# WL_1_2G.net
KiCad netlist of a schematic drawn in Altium Designer
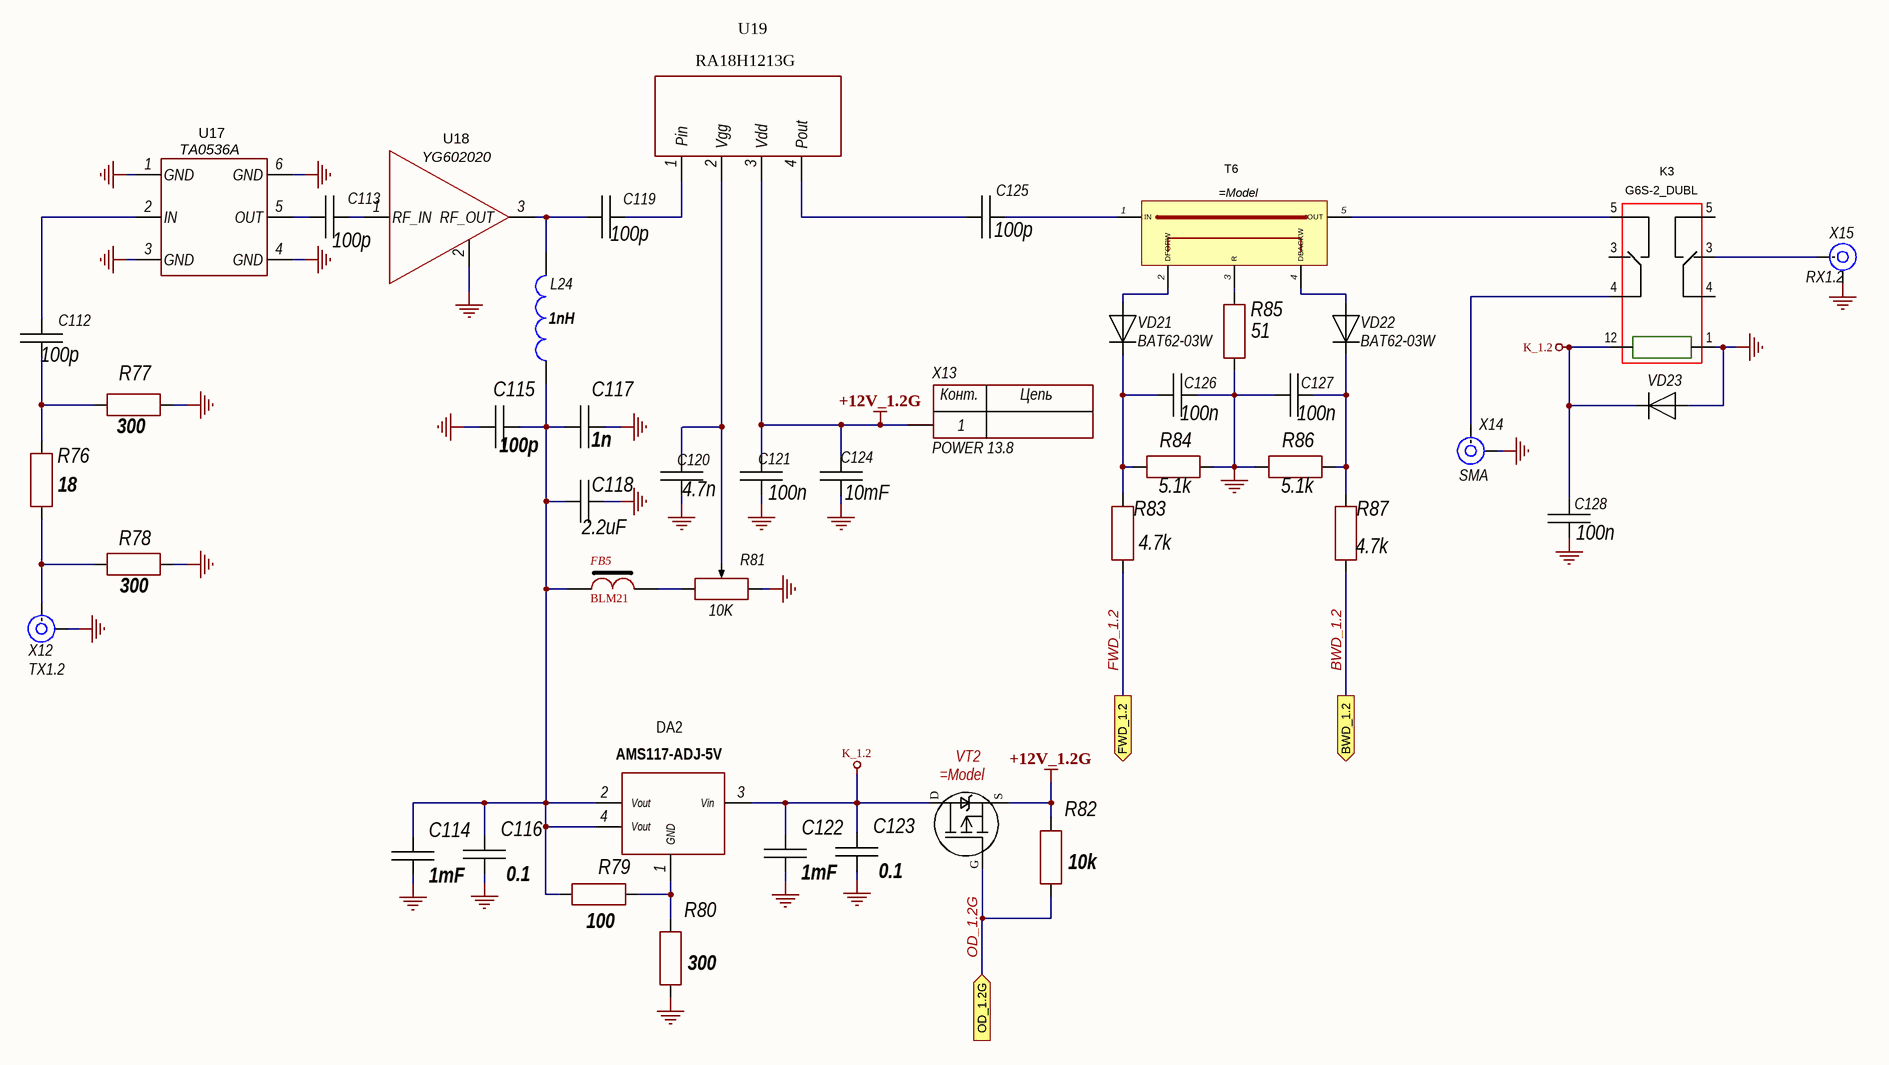
[diagram p0: WL_1.2G.SchDoc]

(export (version "E")
  (design (tool "Eeschema 10.0.6"))
  (components
    (comp (ref "C112")
      (value "100p")
      (footprint "standard:CH0603C")
      (libsource (lib "Discrete") (part "Capacitor"))
    )
    (comp (ref "C113")
      (value "100p")
      (footprint "standard:CH0603C")
      (libsource (lib "Discrete") (part "Capacitor"))
    )
    (comp (ref "C114")
      (value "1mF")
      (footprint "standard:CH0603C")
      (libsource (lib "Discrete") (part "Capacitor"))
    )
    (comp (ref "C115")
      (value "100p")
      (footprint "standard:CH0603C")
      (libsource (lib "Discrete") (part "Capacitor"))
    )
    (comp (ref "C116")
      (value "0.1")
      (footprint "standard:CH0805C")
      (libsource (lib "Discrete") (part "Capacitor"))
    )
    (comp (ref "C117")
      (value "1n")
      (footprint "standard:CH0603C")
      (libsource (lib "Discrete") (part "Capacitor"))
    )
    (comp (ref "C118")
      (value "2.2uF")
      (footprint "standard:CH0603C")
      (libsource (lib "Discrete") (part "Capacitor"))
    )
    (comp (ref "C119")
      (value "100p")
      (footprint "standard:CH0805C")
      (libsource (lib "Discrete") (part "Capacitor"))
    )
    (comp (ref "C120")
      (value "4.7n")
      (footprint "standard:CH0805C")
      (libsource (lib "Discrete") (part "Capacitor"))
    )
    (comp (ref "C121")
      (value "100n")
      (footprint "standard:CH1206C")
      (libsource (lib "Discrete") (part "Capacitor"))
    )
    (comp (ref "C122")
      (value "1mF")
      (footprint "standard:CH0805C")
      (libsource (lib "Discrete") (part "Capacitor"))
    )
    (comp (ref "C123")
      (value "0.1")
      (footprint "standard:CH0805C")
      (libsource (lib "Discrete") (part "Capacitor"))
    )
    (comp (ref "C124")
      (value "10mF")
      (footprint "standard:CH1206C")
      (libsource (lib "Discrete") (part "Capacitor"))
    )
    (comp (ref "C125")
      (value "100p")
      (footprint "standard:CH1210C")
      (libsource (lib "Discrete") (part "Capacitor"))
    )
    (comp (ref "C126")
      (value "100n")
      (footprint "standard:CH0603C")
      (libsource (lib "Discrete") (part "Capacitor"))
    )
    (comp (ref "C127")
      (value "100n")
      (footprint "standard:CH0603C")
      (libsource (lib "Discrete") (part "Capacitor"))
    )
    (comp (ref "C128")
      (value "100n")
      (footprint "standard:CH0805C")
      (libsource (lib "Discrete") (part "Capacitor"))
    )
    (comp (ref "DA2") (value "AMS117-ADJ-5V") (footprint "SOT223") (libsource (lib "Analog") (part "AMS117")))
    (comp (ref "FB5") (value "BLM21") (footprint "CH0805L") (libsource (lib "Discrete") (part "FB-1")))
    (comp (ref "K3")
      (value "G6S-2_DUBL")
      (footprint "G6S-2_DUBL")
      (libsource (lib "Relay") (part "G6S-2_DUBL"))
    )
    (comp (ref "L24")
      (value "1nH")
      (footprint "katuhka")
      (libsource (lib "Transformers") (part "Inductor ring"))
    )
    (comp (ref "R76")
      (value "18")
      (footprint "standard:CH0603R")
      (libsource (lib "Discrete") (part "Resistor"))
    )
    (comp (ref "R77") (value "300") (footprint "standard:CH0603R") (libsource (lib "") (part "Resistor_2")))
    (comp (ref "R78") (value "300") (footprint "standard:CH0603R") (libsource (lib "") (part "Resistor_2")))
    (comp (ref "R79") (value "100") (footprint "standard:CH0805R") (libsource (lib "") (part "Resistor_2")))
    (comp (ref "R80") (value "300") (footprint "standard:CH0805R") (libsource (lib "") (part "Resistor_1")))
    (comp (ref "R81")
      (value "10K")
      (footprint "custom:RES: 3296W")
      (libsource (lib "Discrete") (part "ADJ resistor"))
    )
    (comp (ref "R82") (value "10k") (footprint "standard:CH0805R") (libsource (lib "") (part "Resistor_1")))
    (comp (ref "R83")
      (value "4.7k")
      (footprint "standard:CH0603R")
      (libsource (lib "Discrete") (part "Resistor"))
    )
    (comp (ref "R84") (value "5.1k") (footprint "standard:CH0603R") (libsource (lib "") (part "Resistor_2")))
    (comp (ref "R85") (value "51") (footprint "standard:CH1206R") (libsource (lib "") (part "Resistor_1")))
    (comp (ref "R86") (value "5.1k") (footprint "standard:CH0603R") (libsource (lib "") (part "Resistor_2")))
    (comp (ref "R87")
      (value "4.7k")
      (footprint "standard:CH0603R")
      (libsource (lib "Discrete") (part "Resistor"))
    )
    (comp (ref "T6") (value "~") (footprint "SWR_D") (libsource (lib "Transformers") (part "VHF_KSV1")))
    (comp (ref "U17") (value "TA0536A") (footprint "MA08803") (libsource (lib "Digital") (part "TAU692")))
    (comp (ref "U18")
      (value "YG602020")
      (footprint "SOT89_123")
      (libsource (lib "Digital") (part "YG602020"))
    )
    (comp (ref "U19")
      (value "RA18H1213G")
      (footprint "RA80H1415M1 - duplicate")
      (libsource (lib "Digital") (part "RA80H1415M1"))
    )
    (comp (ref "VD21") (value "BAT62-03W") (footprint "1N4148") (libsource (lib "Diods") (part "Diod")))
    (comp (ref "VD22") (value "BAT62-03W") (footprint "1N4148") (libsource (lib "Diods") (part "Diod")))
    (comp (ref "VD23") (value "~") (footprint "1N4148") (libsource (lib "Diods") (part "Diod")))
    (comp (ref "VT2") (value "~") (footprint "SOT23_132") (libsource (lib "Transistor") (part "P-KANAL")))
    (comp (ref "X12")
      (value "TX1.2")
      (footprint "CON: u.Fl")
      (description "RF")
      (libsource (lib "Connectors") (part "SMA"))
    )
    (comp (ref "X13")
      (value "POWER 13.8")
      (footprint "CON: KNIFE_5MM")
      (libsource (lib "Connectors") (part "1-Connector"))
    )
    (comp (ref "X14")
      (value "SMA")
      (footprint "custom:CON: SMA")
      (description "RF")
      (libsource (lib "Connectors") (part "SMA"))
    )
    (comp (ref "X15")
      (value "RX1.2")
      (footprint "CON: u.Fl")
      (description "RF")
      (libsource (lib "Connectors") (part "SMA"))
    )
  )
  (nets
    (net (code "1") (name "+12V_1.2G") (class "Default")
      (node (ref "C121") (pin "2") (pinfunction "2_2") (pintype "power_in"))
      (node (ref "C124") (pin "2") (pinfunction "2_2") (pintype "power_in"))
      (node (ref "R82") (pin "2") (pinfunction "2_2") (pintype "passive"))
      (node (ref "U19") (pin "3") (pinfunction "Vdd_3") (pintype "passive"))
      (node (ref "VT2") (pin "2") (pinfunction "Исток_2") (pintype "passive"))
      (node (ref "X13") (pin "1") (pinfunction "1_1") (pintype "passive"))
    )
    (net (code "2") (name "/BWD_1.2") (class "Default")
      (node (ref "R87") (pin "2") (pinfunction "2_2") (pintype "passive"))
    )
    (net (code "3") (name "/FWD_1.2") (class "Default")
      (node (ref "R83") (pin "2") (pinfunction "2_2") (pintype "passive"))
    )
    (net (code "4") (name "/OD_1.2G") (class "Default")
      (node (ref "R82") (pin "1") (pinfunction "1_1") (pintype "passive"))
      (node (ref "VT2") (pin "1") (pinfunction "Затвор(Gate)_1") (pintype "passive"))
    )
    (net (code "5") (name "GND") (class "Default")
      (node (ref "C114") (pin "1") (pinfunction "1_1") (pintype "power_in"))
      (node (ref "C115") (pin "2") (pinfunction "2_2") (pintype "power_in"))
      (node (ref "C116") (pin "1") (pinfunction "1_1") (pintype "power_in"))
      (node (ref "C117") (pin "2") (pinfunction "2_2") (pintype "power_in"))
      (node (ref "C118") (pin "2") (pinfunction "2_2") (pintype "power_in"))
      (node (ref "C120") (pin "1") (pinfunction "1_1") (pintype "power_in"))
      (node (ref "C121") (pin "1") (pinfunction "1_1") (pintype "power_in"))
      (node (ref "C122") (pin "1") (pinfunction "1_1") (pintype "power_in"))
      (node (ref "C123") (pin "1") (pinfunction "1_1") (pintype "power_in"))
      (node (ref "C124") (pin "1") (pinfunction "1_1") (pintype "power_in"))
      (node (ref "C126") (pin "1") (pinfunction "1_1") (pintype "power_in"))
      (node (ref "C127") (pin "2") (pinfunction "2_2") (pintype "power_in"))
      (node (ref "C128") (pin "2") (pinfunction "2_2") (pintype "power_in"))
      (node (ref "K3") (pin "1") (pinfunction "1_1") (pintype "passive"))
      (node (ref "R77") (pin "1") (pinfunction "1_1") (pintype "passive"))
      (node (ref "R78") (pin "1") (pinfunction "1_1") (pintype "passive"))
      (node (ref "R80") (pin "1") (pinfunction "1_1") (pintype "passive"))
      (node (ref "R81") (pin "1") (pinfunction "1_1") (pintype "passive"))
      (node (ref "R84") (pin "1") (pinfunction "1_1") (pintype "passive"))
      (node (ref "R85") (pin "1") (pinfunction "1_1") (pintype "passive"))
      (node (ref "R86") (pin "2") (pinfunction "2_2") (pintype "passive"))
      (node (ref "U17") (pin "1") (pinfunction "GND_1") (pintype "passive"))
      (node (ref "U17") (pin "3") (pinfunction "GND_3") (pintype "passive"))
      (node (ref "U17") (pin "4") (pinfunction "GND_4") (pintype "passive"))
      (node (ref "U17") (pin "6") (pinfunction "GND_6") (pintype "passive"))
      (node (ref "U18") (pin "2") (pinfunction "GND_2") (pintype "passive"))
      (node (ref "VD23") (pin "1") (pinfunction "1_1") (pintype "passive"))
      (node (ref "X12") (pin "2") (pinfunction "IN_2") (pintype "passive"))
      (node (ref "X14") (pin "2") (pinfunction "IN_2") (pintype "passive"))
      (node (ref "X15") (pin "2") (pinfunction "IN_2") (pintype "passive"))
    )
    (net (code "6") (name "K_1.2") (class "Default")
      (node (ref "C122") (pin "2") (pinfunction "2_2") (pintype "power_in"))
      (node (ref "C123") (pin "2") (pinfunction "2_2") (pintype "power_in"))
      (node (ref "C128") (pin "1") (pinfunction "1_1") (pintype "power_in"))
      (node (ref "DA2") (pin "3") (pinfunction "Vin_3") (pintype "passive"))
      (node (ref "K3") (pin "12") (pinfunction "12_12") (pintype "passive"))
      (node (ref "VD23") (pin "2") (pinfunction "2_2") (pintype "passive"))
      (node (ref "VT2") (pin "3") (pinfunction "Сток_3") (pintype "passive"))
    )
    (net (code "7") (name "Net-(C112-Pad2)") (class "Default")
      (node (ref "C112") (pin "2") (pinfunction "2_2") (pintype "power_in"))
      (node (ref "R76") (pin "1") (pinfunction "1_1") (pintype "passive"))
      (node (ref "R77") (pin "2") (pinfunction "2_2") (pintype "passive"))
    )
    (net (code "8") (name "Net-(C114-Pad2)") (class "Default")
      (node (ref "C114") (pin "2") (pinfunction "2_2") (pintype "power_in"))
      (node (ref "C115") (pin "1") (pinfunction "1_1") (pintype "power_in"))
      (node (ref "C116") (pin "2") (pinfunction "2_2") (pintype "power_in"))
      (node (ref "C117") (pin "1") (pinfunction "1_1") (pintype "power_in"))
      (node (ref "C118") (pin "1") (pinfunction "1_1") (pintype "power_in"))
      (node (ref "DA2") (pin "2") (pinfunction "Vout_2") (pintype "passive"))
      (node (ref "DA2") (pin "4") (pinfunction "Vout_4") (pintype "passive"))
      (node (ref "FB5") (pin "1") (pinfunction "1_1") (pintype "passive"))
      (node (ref "L24") (pin "2") (pinfunction "2_2") (pintype "passive"))
      (node (ref "R79") (pin "2") (pinfunction "2_2") (pintype "passive"))
    )
    (net (code "9") (name "Net-(C126-Pad2)") (class "Default")
      (node (ref "C126") (pin "2") (pinfunction "2_2") (pintype "power_in"))
      (node (ref "R83") (pin "1") (pinfunction "1_1") (pintype "passive"))
      (node (ref "R84") (pin "2") (pinfunction "2_2") (pintype "passive"))
      (node (ref "VD21") (pin "2") (pinfunction "2_2") (pintype "passive"))
    )
    (net (code "10") (name "Net-(C127-Pad1)") (class "Default")
      (node (ref "C127") (pin "1") (pinfunction "1_1") (pintype "power_in"))
      (node (ref "R86") (pin "1") (pinfunction "1_1") (pintype "passive"))
      (node (ref "R87") (pin "1") (pinfunction "1_1") (pintype "passive"))
      (node (ref "VD22") (pin "2") (pinfunction "2_2") (pintype "passive"))
    )
    (net (code "11") (name "Net-(DA2-GND)") (class "Default")
      (node (ref "DA2") (pin "1") (pinfunction "GND_1") (pintype "passive"))
      (node (ref "R79") (pin "1") (pinfunction "1_1") (pintype "passive"))
      (node (ref "R80") (pin "2") (pinfunction "2_2") (pintype "passive"))
    )
    (net (code "12") (name "Net-(FB5-Pad2)") (class "Default")
      (node (ref "FB5") (pin "2") (pinfunction "2_2") (pintype "passive"))
      (node (ref "R81") (pin "3") (pinfunction "3_3") (pintype "passive"))
    )
    (net (code "13") (name "Net-(K3-Pad3)_1") (class "Default")
      (node (ref "K3") (pin "3") (pinfunction "3_3") (pintype "passive"))
      (node (ref "X15") (pin "1") (pinfunction "IN_1") (pintype "passive"))
    )
    (net (code "14") (name "Net-(K3-Pad4)") (class "Default")
      (node (ref "K3") (pin "4") (pinfunction "4_4") (pintype "passive"))
      (node (ref "X14") (pin "1") (pinfunction "IN_1") (pintype "passive"))
    )
    (net (code "15") (name "Net-(R76-Pad2)") (class "Default")
      (node (ref "R76") (pin "2") (pinfunction "2_2") (pintype "passive"))
      (node (ref "R78") (pin "2") (pinfunction "2_2") (pintype "passive"))
      (node (ref "X12") (pin "1") (pinfunction "IN_1") (pintype "passive"))
    )
    (net (code "16") (name "Net-(T6-DBACKW)") (class "Default")
      (node (ref "T6") (pin "4") (pinfunction "DBACKW_4") (pintype "passive"))
      (node (ref "VD22") (pin "1") (pinfunction "1_1") (pintype "passive"))
    )
    (net (code "17") (name "Net-(T6-DFORW)") (class "Default")
      (node (ref "T6") (pin "2") (pinfunction "DFORW_2") (pintype "passive"))
      (node (ref "VD21") (pin "1") (pinfunction "1_1") (pintype "passive"))
    )
    (net (code "18") (name "Net-(T6-IN)") (class "Default")
      (node (ref "C125") (pin "1") (pinfunction "1_1") (pintype "power_in"))
      (node (ref "T6") (pin "1") (pinfunction "IN_1") (pintype "passive"))
    )
    (net (code "19") (name "Net-(T6-OUT)") (class "Default")
      (node (ref "K3") (pin "5") (pinfunction "5_5") (pintype "passive"))
      (node (ref "T6") (pin "5") (pinfunction "OUT_5") (pintype "passive"))
    )
    (net (code "20") (name "Net-(T6-R)") (class "Default")
      (node (ref "R85") (pin "2") (pinfunction "2_2") (pintype "passive"))
      (node (ref "T6") (pin "3") (pinfunction "R_3") (pintype "passive"))
    )
    (net (code "21") (name "Net-(U17-IN)") (class "Default")
      (node (ref "C112") (pin "1") (pinfunction "1_1") (pintype "power_in"))
      (node (ref "U17") (pin "2") (pinfunction "IN_2") (pintype "passive"))
    )
    (net (code "22") (name "Net-(U17-OUT)") (class "Default")
      (node (ref "C113") (pin "2") (pinfunction "2_2") (pintype "power_in"))
      (node (ref "U17") (pin "5") (pinfunction "OUT_5") (pintype "passive"))
    )
    (net (code "23") (name "Net-(U18-RF_IN)") (class "Default")
      (node (ref "C113") (pin "1") (pinfunction "1_1") (pintype "power_in"))
      (node (ref "U18") (pin "1") (pinfunction "RF_IN_1") (pintype "passive"))
    )
    (net (code "24") (name "Net-(U18-RF_OUT)") (class "Default")
      (node (ref "C119") (pin "2") (pinfunction "2_2") (pintype "power_in"))
      (node (ref "L24") (pin "1") (pinfunction "1_1") (pintype "passive"))
      (node (ref "U18") (pin "3") (pinfunction "RF_OUT_3") (pintype "passive"))
    )
    (net (code "25") (name "Net-(U19-Pin)") (class "Default")
      (node (ref "C119") (pin "1") (pinfunction "1_1") (pintype "power_in"))
      (node (ref "U19") (pin "1") (pinfunction "Pin_1") (pintype "passive"))
    )
    (net (code "26") (name "Net-(U19-Pout)") (class "Default")
      (node (ref "C125") (pin "2") (pinfunction "2_2") (pintype "power_in"))
      (node (ref "U19") (pin "4") (pinfunction "Pout_4") (pintype "passive"))
    )
    (net (code "27") (name "Net-(U19-Vgg)") (class "Default")
      (node (ref "C120") (pin "2") (pinfunction "2_2") (pintype "power_in"))
      (node (ref "R81") (pin "2") (pinfunction "2_2") (pintype "passive"))
      (node (ref "U19") (pin "2") (pinfunction "Vgg_2") (pintype "passive"))
    )
    (net (code "28") (name "unconnected-(K3-Pad3)") (class "Default")
      (node (ref "K3") (pin "3") (pinfunction "3_3") (pintype "passive"))
    )
    (net (code "29") (name "unconnected-(K3-Pad4)_1") (class "Default")
      (node (ref "K3") (pin "4") (pinfunction "4_4") (pintype "passive"))
    )
    (net (code "30") (name "unconnected-(K3-Pad5)") (class "Default")
      (node (ref "K3") (pin "5") (pinfunction "5_5") (pintype "passive"))
    )
  )
)
